# spindle_light.net
KiCad netlist of a schematic drawn in EAGLE
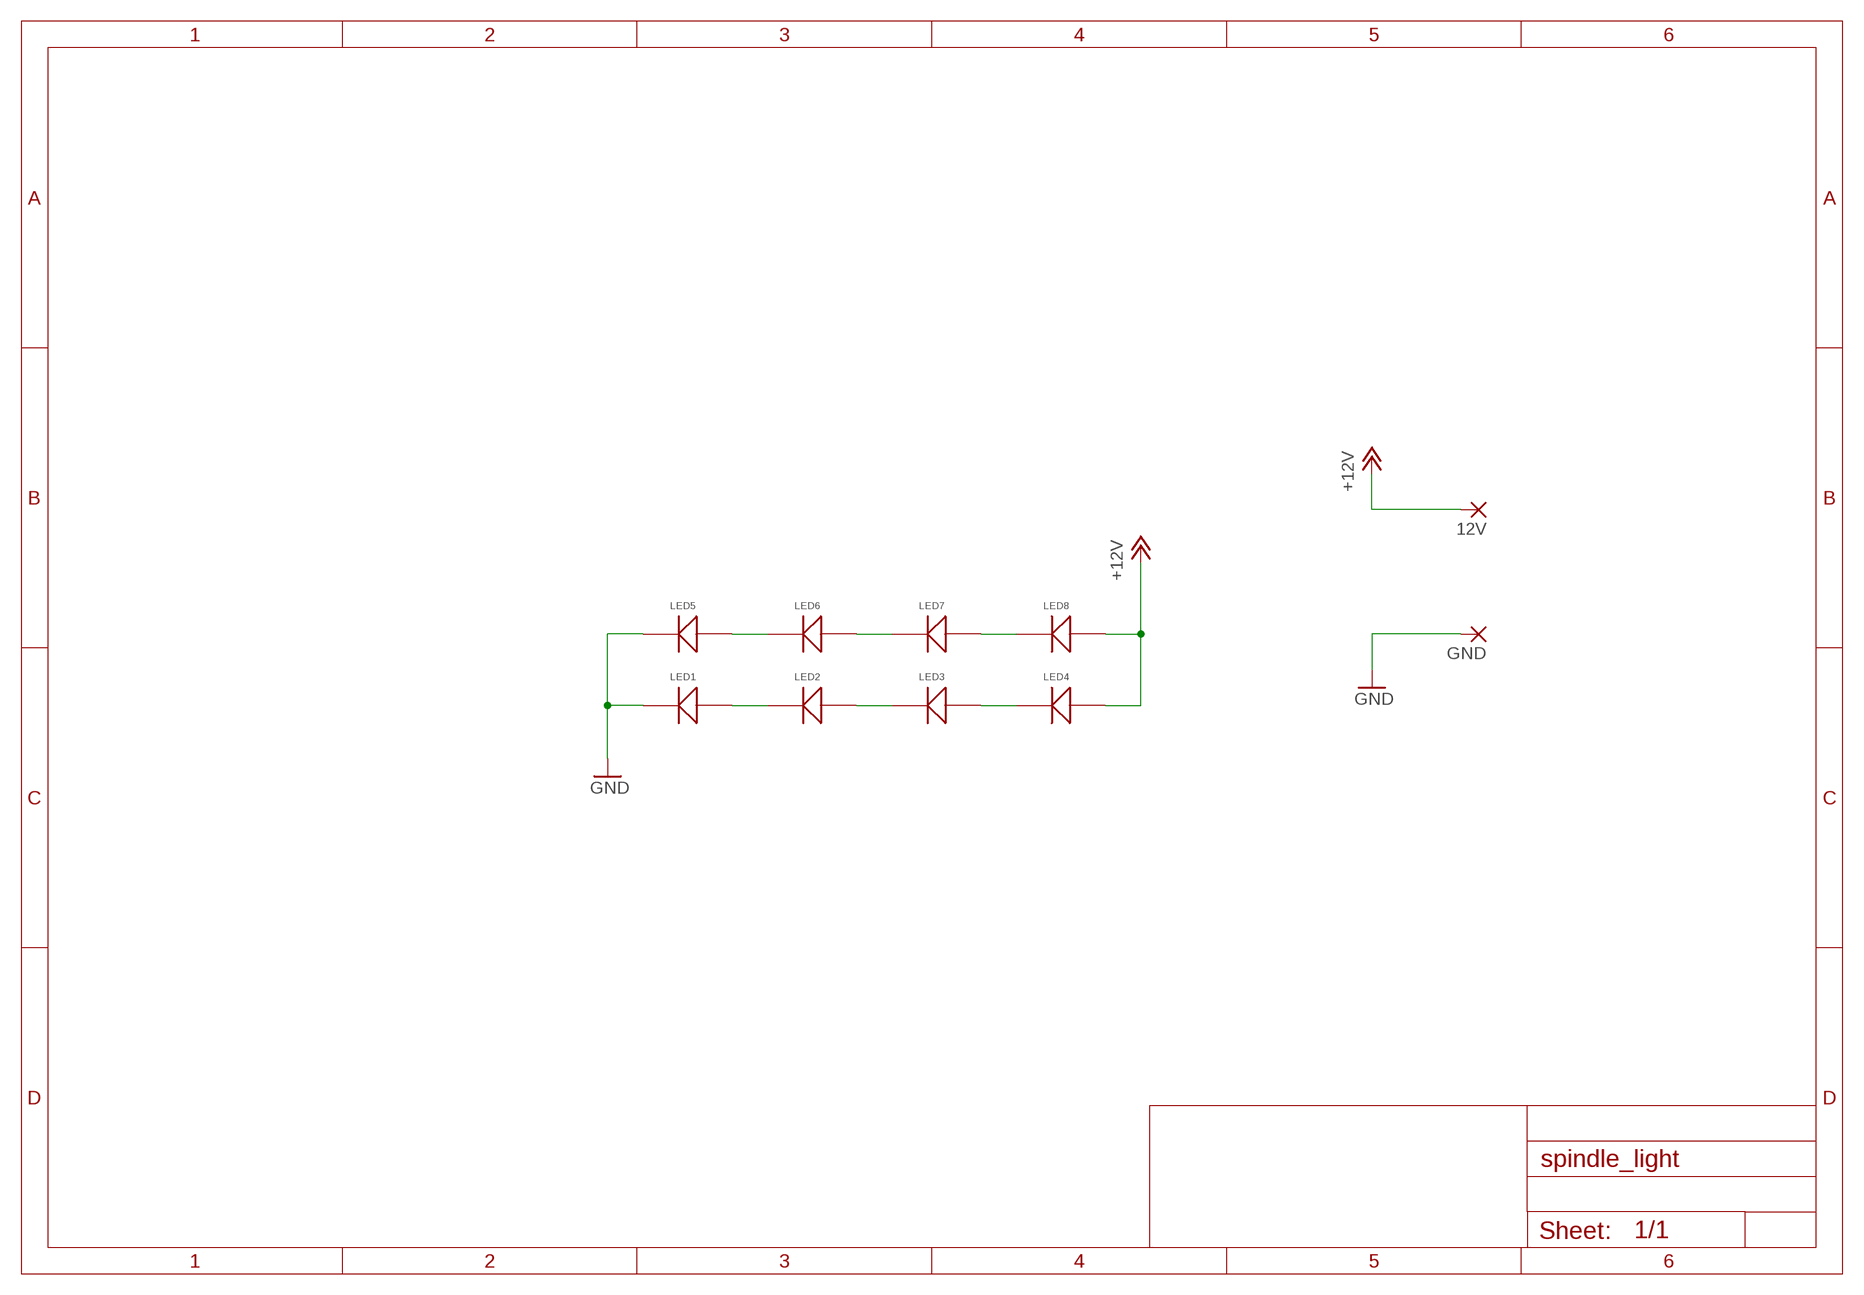
[diagram p0: schematic, sheet 1]

(export (version "E")
  (design (tool "Eeschema 10.0.6"))
  (components
    (comp (ref "12V")
      (value "SMD5")
      (footprint "eagle-import:SMD2,54-5,08")
      (libsource (lib "eagle-import") (part "SMD5"))
    )
    (comp (ref "GND")
      (value "SMD5")
      (footprint "eagle-import:SMD2,54-5,08")
      (libsource (lib "eagle-import") (part "SMD5"))
    )
    (comp (ref "LED1")
      (value "RF-45HA50DS-EE-Y")
      (footprint "eagle-import:5050LED")
      (libsource (lib "eagle-import") (part "RF-45HA50DS-EE-Y"))
    )
    (comp (ref "LED2")
      (value "RF-45HA50DS-EE-Y")
      (footprint "eagle-import:5050LED")
      (libsource (lib "eagle-import") (part "RF-45HA50DS-EE-Y"))
    )
    (comp (ref "LED3")
      (value "RF-45HA50DS-EE-Y")
      (footprint "eagle-import:5050LED")
      (libsource (lib "eagle-import") (part "RF-45HA50DS-EE-Y"))
    )
    (comp (ref "LED4")
      (value "RF-45HA50DS-EE-Y")
      (footprint "eagle-import:5050LED")
      (libsource (lib "eagle-import") (part "RF-45HA50DS-EE-Y"))
    )
    (comp (ref "LED5")
      (value "RF-45HA50DS-EE-Y")
      (footprint "eagle-import:5050LED")
      (libsource (lib "eagle-import") (part "RF-45HA50DS-EE-Y"))
    )
    (comp (ref "LED6")
      (value "RF-45HA50DS-EE-Y")
      (footprint "eagle-import:5050LED")
      (libsource (lib "eagle-import") (part "RF-45HA50DS-EE-Y"))
    )
    (comp (ref "LED7")
      (value "RF-45HA50DS-EE-Y")
      (footprint "eagle-import:5050LED")
      (libsource (lib "eagle-import") (part "RF-45HA50DS-EE-Y"))
    )
    (comp (ref "LED8")
      (value "RF-45HA50DS-EE-Y")
      (footprint "eagle-import:5050LED")
      (libsource (lib "eagle-import") (part "RF-45HA50DS-EE-Y"))
    )
  )
  (nets
    (net (code "1") (name "+12V") (class "Default")
      (node (ref "12V") (pin "1") (pinfunction "P_1") (pintype "passive"))
      (node (ref "LED4") (pin "P$4") (pinfunction "P$1_P$4") (pintype "bidirectional"))
      (node (ref "LED4") (pin "P$5") (pinfunction "P$1_P$5") (pintype "bidirectional"))
      (node (ref "LED4") (pin "P$6") (pinfunction "P$1_P$6") (pintype "bidirectional"))
      (node (ref "LED8") (pin "P$4") (pinfunction "P$1_P$4") (pintype "bidirectional"))
      (node (ref "LED8") (pin "P$5") (pinfunction "P$1_P$5") (pintype "bidirectional"))
      (node (ref "LED8") (pin "P$6") (pinfunction "P$1_P$6") (pintype "bidirectional"))
    )
    (net (code "2") (name "GND") (class "Default")
      (node (ref "GND") (pin "1") (pinfunction "P_1") (pintype "passive"))
      (node (ref "LED1") (pin "P$1") (pinfunction "P$2_P$1") (pintype "bidirectional"))
      (node (ref "LED1") (pin "P$2") (pinfunction "P$2_P$2") (pintype "bidirectional"))
      (node (ref "LED1") (pin "P$3") (pinfunction "P$2_P$3") (pintype "bidirectional"))
      (node (ref "LED5") (pin "P$1") (pinfunction "P$2_P$1") (pintype "bidirectional"))
      (node (ref "LED5") (pin "P$2") (pinfunction "P$2_P$2") (pintype "bidirectional"))
      (node (ref "LED5") (pin "P$3") (pinfunction "P$2_P$3") (pintype "bidirectional"))
    )
    (net (code "3") (name "Net-(LED1-P$1-PadP$4)") (class "Default")
      (node (ref "LED1") (pin "P$4") (pinfunction "P$1_P$4") (pintype "bidirectional"))
      (node (ref "LED1") (pin "P$5") (pinfunction "P$1_P$5") (pintype "bidirectional"))
      (node (ref "LED1") (pin "P$6") (pinfunction "P$1_P$6") (pintype "bidirectional"))
      (node (ref "LED2") (pin "P$1") (pinfunction "P$2_P$1") (pintype "bidirectional"))
      (node (ref "LED2") (pin "P$2") (pinfunction "P$2_P$2") (pintype "bidirectional"))
      (node (ref "LED2") (pin "P$3") (pinfunction "P$2_P$3") (pintype "bidirectional"))
    )
    (net (code "4") (name "Net-(LED2-P$1-PadP$4)") (class "Default")
      (node (ref "LED2") (pin "P$4") (pinfunction "P$1_P$4") (pintype "bidirectional"))
      (node (ref "LED2") (pin "P$5") (pinfunction "P$1_P$5") (pintype "bidirectional"))
      (node (ref "LED2") (pin "P$6") (pinfunction "P$1_P$6") (pintype "bidirectional"))
      (node (ref "LED3") (pin "P$1") (pinfunction "P$2_P$1") (pintype "bidirectional"))
      (node (ref "LED3") (pin "P$2") (pinfunction "P$2_P$2") (pintype "bidirectional"))
      (node (ref "LED3") (pin "P$3") (pinfunction "P$2_P$3") (pintype "bidirectional"))
    )
    (net (code "5") (name "Net-(LED3-P$1-PadP$4)") (class "Default")
      (node (ref "LED3") (pin "P$4") (pinfunction "P$1_P$4") (pintype "bidirectional"))
      (node (ref "LED3") (pin "P$5") (pinfunction "P$1_P$5") (pintype "bidirectional"))
      (node (ref "LED3") (pin "P$6") (pinfunction "P$1_P$6") (pintype "bidirectional"))
      (node (ref "LED4") (pin "P$1") (pinfunction "P$2_P$1") (pintype "bidirectional"))
      (node (ref "LED4") (pin "P$2") (pinfunction "P$2_P$2") (pintype "bidirectional"))
      (node (ref "LED4") (pin "P$3") (pinfunction "P$2_P$3") (pintype "bidirectional"))
    )
    (net (code "6") (name "Net-(LED5-P$1-PadP$4)") (class "Default")
      (node (ref "LED5") (pin "P$4") (pinfunction "P$1_P$4") (pintype "bidirectional"))
      (node (ref "LED5") (pin "P$5") (pinfunction "P$1_P$5") (pintype "bidirectional"))
      (node (ref "LED5") (pin "P$6") (pinfunction "P$1_P$6") (pintype "bidirectional"))
      (node (ref "LED6") (pin "P$1") (pinfunction "P$2_P$1") (pintype "bidirectional"))
      (node (ref "LED6") (pin "P$2") (pinfunction "P$2_P$2") (pintype "bidirectional"))
      (node (ref "LED6") (pin "P$3") (pinfunction "P$2_P$3") (pintype "bidirectional"))
    )
    (net (code "7") (name "Net-(LED6-P$1-PadP$4)") (class "Default")
      (node (ref "LED6") (pin "P$4") (pinfunction "P$1_P$4") (pintype "bidirectional"))
      (node (ref "LED6") (pin "P$5") (pinfunction "P$1_P$5") (pintype "bidirectional"))
      (node (ref "LED6") (pin "P$6") (pinfunction "P$1_P$6") (pintype "bidirectional"))
      (node (ref "LED7") (pin "P$1") (pinfunction "P$2_P$1") (pintype "bidirectional"))
      (node (ref "LED7") (pin "P$2") (pinfunction "P$2_P$2") (pintype "bidirectional"))
      (node (ref "LED7") (pin "P$3") (pinfunction "P$2_P$3") (pintype "bidirectional"))
    )
    (net (code "8") (name "Net-(LED7-P$1-PadP$4)") (class "Default")
      (node (ref "LED7") (pin "P$4") (pinfunction "P$1_P$4") (pintype "bidirectional"))
      (node (ref "LED7") (pin "P$5") (pinfunction "P$1_P$5") (pintype "bidirectional"))
      (node (ref "LED7") (pin "P$6") (pinfunction "P$1_P$6") (pintype "bidirectional"))
      (node (ref "LED8") (pin "P$1") (pinfunction "P$2_P$1") (pintype "bidirectional"))
      (node (ref "LED8") (pin "P$2") (pinfunction "P$2_P$2") (pintype "bidirectional"))
      (node (ref "LED8") (pin "P$3") (pinfunction "P$2_P$3") (pintype "bidirectional"))
    )
  )
)
